# tutorial2.net
KiCad netlist of a schematic drawn in EAGLE
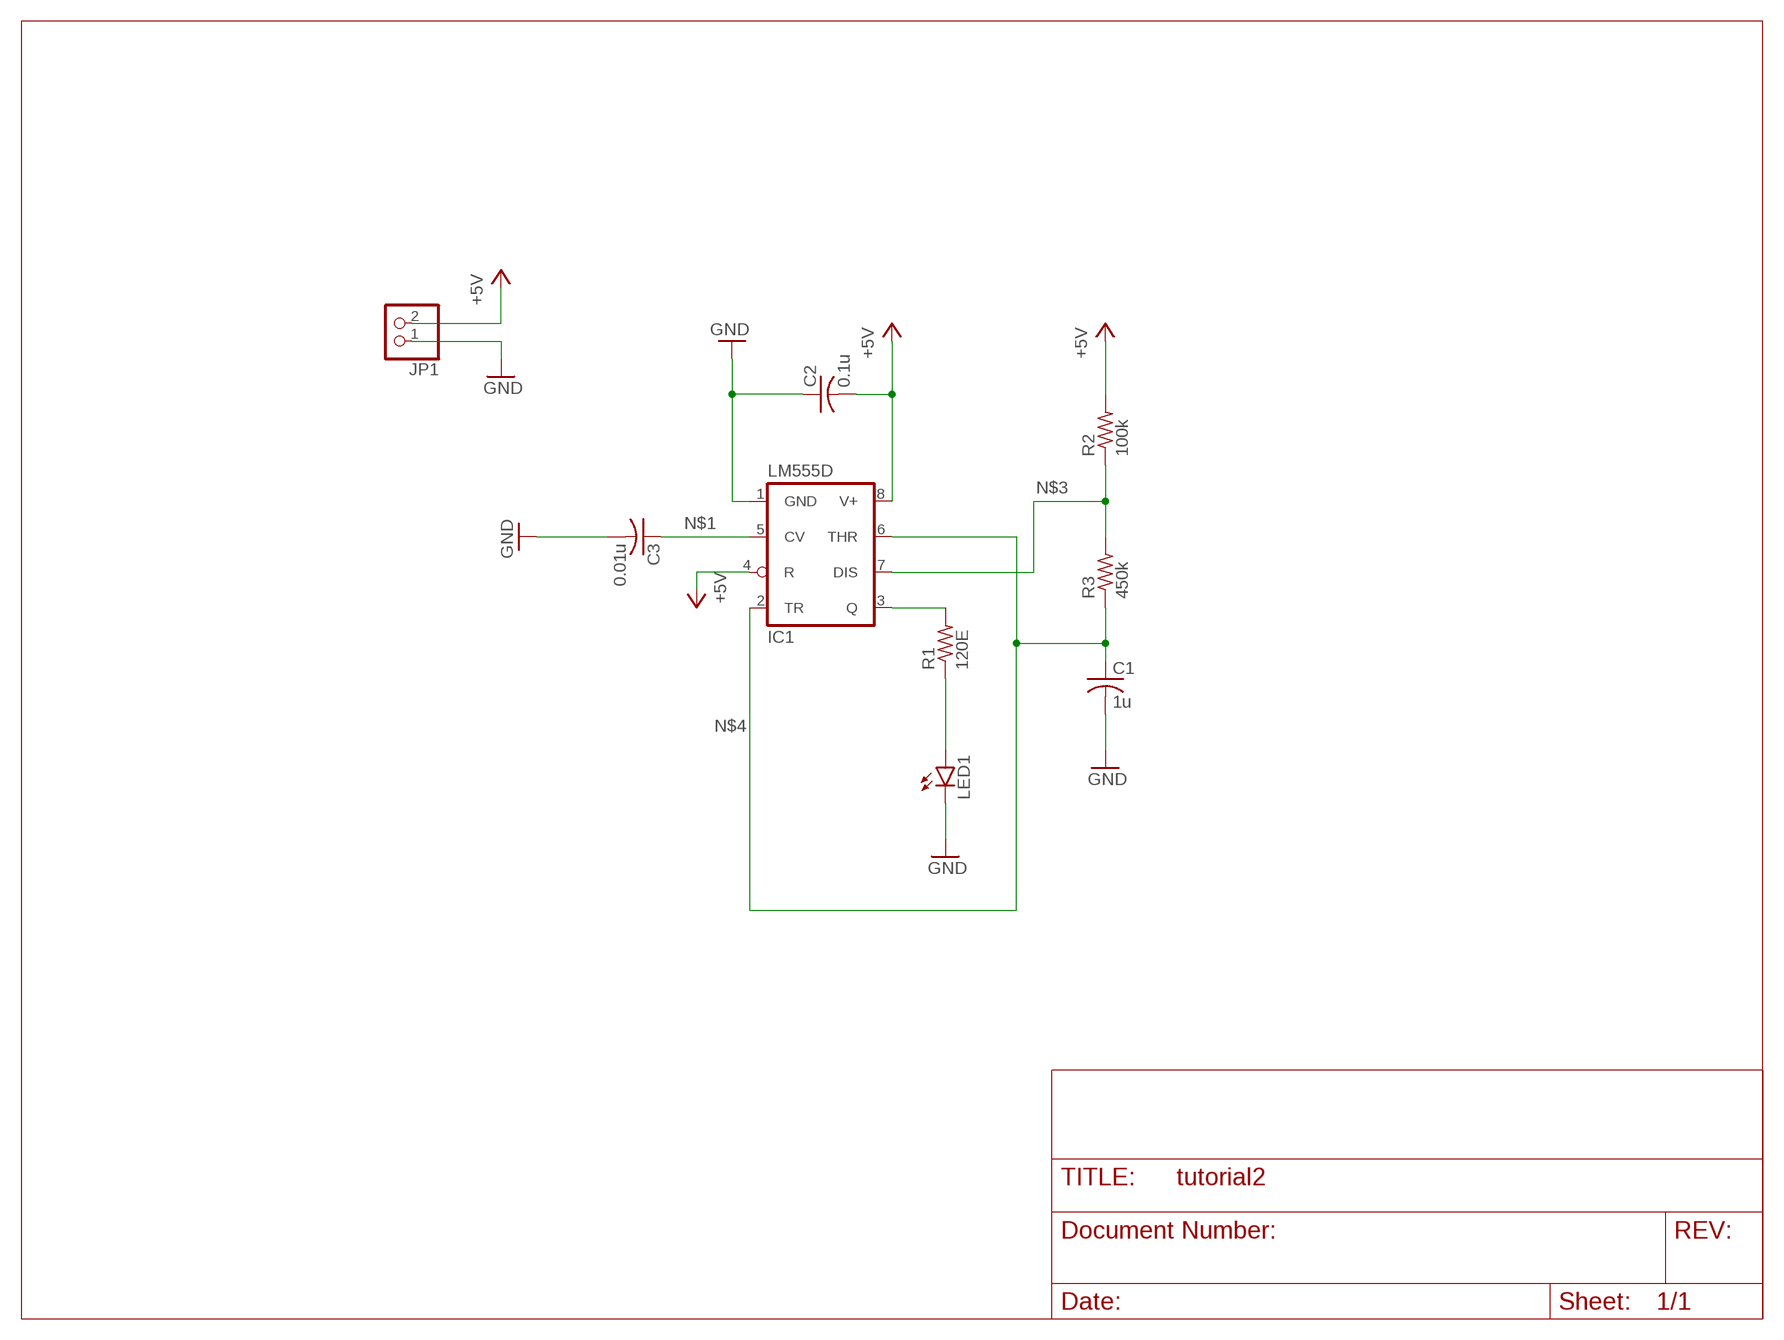
[diagram p0: schematic, sheet 1]

(export (version "E")
  (design (tool "Eeschema 10.0.6"))
  (components
    (comp (ref "C1")
      (value "1u")
      (footprint "eagle-import:C0805")
      (libsource (lib "eagle-import") (part "C-USC0805"))
    )
    (comp (ref "C2")
      (value "0.1u")
      (footprint "eagle-import:C0805")
      (libsource (lib "eagle-import") (part "C-USC0805"))
    )
    (comp (ref "C3")
      (value "0.01u")
      (footprint "eagle-import:C0805")
      (libsource (lib "eagle-import") (part "C-USC0805"))
    )
    (comp (ref "IC1")
      (value "LM555D")
      (footprint "eagle-import:SO08")
      (libsource (lib "eagle-import") (part "555DLM"))
    )
    (comp (ref "JP1")
      (value "PINHD-1X2")
      (footprint "eagle-import:1X02")
      (libsource (lib "eagle-import") (part "PINHD-1X2"))
    )
    (comp (ref "LED1")
      (value "LED5MM")
      (footprint "eagle-import:LED5MM")
      (libsource (lib "eagle-import") (part "LED5MM"))
    )
    (comp (ref "R1")
      (value "120E")
      (footprint "eagle-import:R0805")
      (libsource (lib "eagle-import") (part "R-US_R0805"))
    )
    (comp (ref "R2")
      (value "100k")
      (footprint "eagle-import:R0805")
      (libsource (lib "eagle-import") (part "R-US_R0805"))
    )
    (comp (ref "R3")
      (value "450k")
      (footprint "eagle-import:R0805")
      (libsource (lib "eagle-import") (part "R-US_R0805"))
    )
  )
  (nets
    (net (code "1") (name "+5V") (class "Default")
      (node (ref "C2") (pin "2") (pinfunction "2_2") (pintype "passive"))
      (node (ref "IC1") (pin "4") (pinfunction "R_4") (pintype "input"))
      (node (ref "IC1") (pin "8") (pinfunction "V+_8") (pintype "power_in"))
      (node (ref "JP1") (pin "2") (pinfunction "2_2") (pintype "passive"))
      (node (ref "R2") (pin "2") (pinfunction "2_2") (pintype "passive"))
    )
    (net (code "2") (name "/N$1") (class "Default")
      (node (ref "C3") (pin "1") (pinfunction "1_1") (pintype "passive"))
      (node (ref "IC1") (pin "5") (pinfunction "CV_5") (pintype "input"))
    )
    (net (code "3") (name "/N$3") (class "Default")
      (node (ref "IC1") (pin "7") (pinfunction "DIS_7") (pintype "input"))
      (node (ref "R2") (pin "1") (pinfunction "1_1") (pintype "passive"))
      (node (ref "R3") (pin "2") (pinfunction "2_2") (pintype "passive"))
    )
    (net (code "4") (name "/N$4") (class "Default")
      (node (ref "C1") (pin "1") (pinfunction "1_1") (pintype "passive"))
      (node (ref "IC1") (pin "2") (pinfunction "TR_2") (pintype "input"))
      (node (ref "IC1") (pin "6") (pinfunction "THR_6") (pintype "input"))
      (node (ref "R3") (pin "1") (pinfunction "1_1") (pintype "passive"))
    )
    (net (code "5") (name "GND") (class "Default")
      (node (ref "C1") (pin "2") (pinfunction "2_2") (pintype "passive"))
      (node (ref "C2") (pin "1") (pinfunction "1_1") (pintype "passive"))
      (node (ref "C3") (pin "2") (pinfunction "2_2") (pintype "passive"))
      (node (ref "IC1") (pin "1") (pinfunction "GND_1") (pintype "power_in"))
      (node (ref "JP1") (pin "1") (pinfunction "1_1") (pintype "passive"))
      (node (ref "LED1") (pin "K") (pinfunction "C_K") (pintype "passive"))
    )
    (net (code "6") (name "Net-(IC1-Q)") (class "Default")
      (node (ref "IC1") (pin "3") (pinfunction "Q_3") (pintype "output"))
      (node (ref "R1") (pin "2") (pinfunction "2_2") (pintype "passive"))
    )
    (net (code "7") (name "Net-(LED1-PadA)") (class "Default")
      (node (ref "LED1") (pin "A") (pinfunction "A_A") (pintype "passive"))
      (node (ref "R1") (pin "1") (pinfunction "1_1") (pintype "passive"))
    )
  )
)
